# Sheet1.net
KiCad netlist of a schematic drawn in Altium Designer
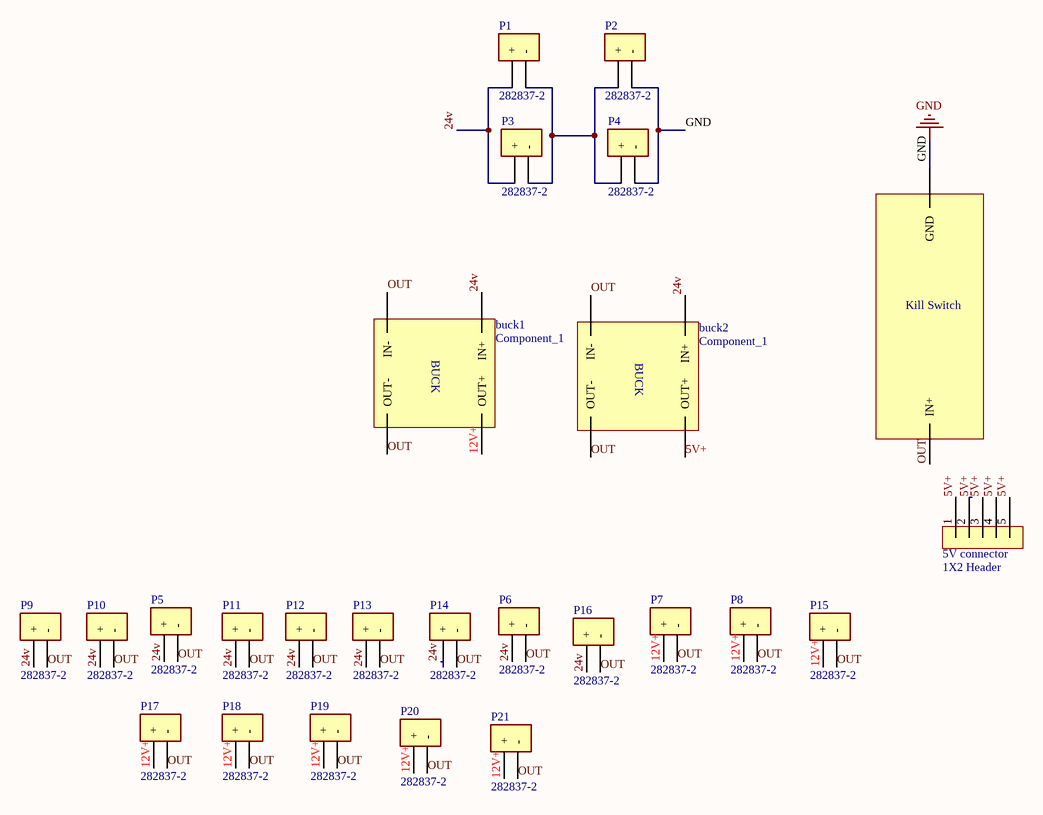
[diagram p0: Sheet1.SchDoc]

(export (version "E")
  (design (tool "Eeschema 10.0.6"))
  (components
    (comp (ref "5V connector")
      (value "1X2 Header")
      (footprint "Connector")
      (fields
        (field (name "MANUFACTURER") "TE Connectivity")
        (field (name "MANUFACTURER PART NUMBER") "640456-4")
      )
      (libsource (lib "282837-2") (part "640456-4"))
    )
    (comp (ref "buck1")
      (value "Component_1")
      (footprint "buck - duplicate")
      (libsource (lib "282837-2") (part "Component_1"))
    )
    (comp (ref "buck2")
      (value "Component_1")
      (footprint "buck - duplicate")
      (libsource (lib "282837-2") (part "Component_1"))
    )
    (comp (ref "KS") (value "KS") (footprint "KS") (libsource (lib "282837-2") (part "KS")))
    (comp (ref "P1")
      (value "282837-2")
      (footprint "TE_282837-2")
      (fields (field (name "MF") "TE Connectivity"))
      (libsource (lib "282837-2") (part "282837-2"))
    )
    (comp (ref "P2")
      (value "282837-2")
      (footprint "TE_282837-2")
      (fields (field (name "MF") "TE Connectivity"))
      (libsource (lib "282837-2") (part "282837-2"))
    )
    (comp (ref "P3")
      (value "282837-2")
      (footprint "TE_282837-2")
      (fields (field (name "MF") "TE Connectivity"))
      (libsource (lib "282837-2") (part "282837-2"))
    )
    (comp (ref "P4")
      (value "282837-2")
      (footprint "TE_282837-2")
      (fields (field (name "MF") "TE Connectivity"))
      (libsource (lib "282837-2") (part "282837-2"))
    )
    (comp (ref "P5")
      (value "282837-2")
      (footprint "TE_282837-2")
      (fields (field (name "MF") "TE Connectivity"))
      (libsource (lib "282837-2") (part "282837-2"))
    )
    (comp (ref "P6")
      (value "282837-2")
      (footprint "TE_282837-2")
      (fields (field (name "MF") "TE Connectivity"))
      (libsource (lib "282837-2") (part "282837-2"))
    )
    (comp (ref "P7")
      (value "282837-2")
      (footprint "TE_282837-2")
      (fields (field (name "MF") "TE Connectivity"))
      (libsource (lib "282837-2") (part "282837-2"))
    )
    (comp (ref "P8")
      (value "282837-2")
      (footprint "TE_282837-2")
      (fields (field (name "MF") "TE Connectivity"))
      (libsource (lib "282837-2") (part "282837-2"))
    )
    (comp (ref "P9")
      (value "282837-2")
      (footprint "TE_282837-2")
      (fields (field (name "MF") "TE Connectivity"))
      (libsource (lib "282837-2") (part "282837-2"))
    )
    (comp (ref "P10")
      (value "282837-2")
      (footprint "TE_282837-2")
      (fields (field (name "MF") "TE Connectivity"))
      (libsource (lib "282837-2") (part "282837-2"))
    )
    (comp (ref "P11")
      (value "282837-2")
      (footprint "TE_282837-2")
      (fields (field (name "MF") "TE Connectivity"))
      (libsource (lib "282837-2") (part "282837-2"))
    )
    (comp (ref "P12")
      (value "282837-2")
      (footprint "TE_282837-2")
      (fields (field (name "MF") "TE Connectivity"))
      (libsource (lib "282837-2") (part "282837-2"))
    )
    (comp (ref "P13")
      (value "282837-2")
      (footprint "TE_282837-2")
      (fields (field (name "MF") "TE Connectivity"))
      (libsource (lib "282837-2") (part "282837-2"))
    )
    (comp (ref "P14")
      (value "282837-2")
      (footprint "TE_282837-2")
      (fields (field (name "MF") "TE Connectivity"))
      (libsource (lib "282837-2") (part "282837-2"))
    )
    (comp (ref "P15")
      (value "282837-2")
      (footprint "TE_282837-2")
      (fields (field (name "MF") "TE Connectivity"))
      (libsource (lib "282837-2") (part "282837-2"))
    )
    (comp (ref "P16")
      (value "282837-2")
      (footprint "TE_282837-2")
      (fields (field (name "MF") "TE Connectivity"))
      (libsource (lib "282837-2") (part "282837-2"))
    )
    (comp (ref "P17")
      (value "282837-2")
      (footprint "TE_282837-2")
      (fields (field (name "MF") "TE Connectivity"))
      (libsource (lib "282837-2") (part "282837-2"))
    )
    (comp (ref "P18")
      (value "282837-2")
      (footprint "TE_282837-2")
      (fields (field (name "MF") "TE Connectivity"))
      (libsource (lib "282837-2") (part "282837-2"))
    )
    (comp (ref "P19")
      (value "282837-2")
      (footprint "TE_282837-2")
      (fields (field (name "MF") "TE Connectivity"))
      (libsource (lib "282837-2") (part "282837-2"))
    )
    (comp (ref "P20")
      (value "282837-2")
      (footprint "TE_282837-2")
      (fields (field (name "MF") "TE Connectivity"))
      (libsource (lib "282837-2") (part "282837-2"))
    )
    (comp (ref "P21")
      (value "282837-2")
      (footprint "TE_282837-2")
      (fields (field (name "MF") "TE Connectivity"))
      (libsource (lib "282837-2") (part "282837-2"))
    )
  )
  (nets
    (net (code "1") (name "/5V+") (class "Default")
      (node (ref "5V connector") (pin "1") (pinfunction "31_1") (pintype "passive"))
      (node (ref "5V connector") (pin "2") (pinfunction "32_2") (pintype "passive"))
      (node (ref "5V connector") (pin "3") (pinfunction "33_3") (pintype "passive"))
      (node (ref "5V connector") (pin "4") (pinfunction "34_4") (pintype "passive"))
      (node (ref "5V connector") (pin "5") (pinfunction "35_5") (pintype "passive"))
      (node (ref "buck2") (pin "4") (pinfunction "OUT+_4") (pintype "passive"))
    )
    (net (code "2") (name "/12V+") (class "Default")
      (node (ref "P15") (pin "1") (pinfunction "+_1") (pintype "passive"))
      (node (ref "P17") (pin "1") (pinfunction "+_1") (pintype "passive"))
      (node (ref "P18") (pin "1") (pinfunction "+_1") (pintype "passive"))
      (node (ref "P19") (pin "1") (pinfunction "+_1") (pintype "passive"))
      (node (ref "P20") (pin "1") (pinfunction "+_1") (pintype "passive"))
      (node (ref "P21") (pin "1") (pinfunction "+_1") (pintype "passive"))
      (node (ref "P7") (pin "1") (pinfunction "+_1") (pintype "passive"))
      (node (ref "P8") (pin "1") (pinfunction "+_1") (pintype "passive"))
      (node (ref "buck1") (pin "4") (pinfunction "OUT+_4") (pintype "passive"))
    )
    (net (code "3") (name "/24v") (class "Default")
      (node (ref "P1") (pin "1") (pinfunction "+_1") (pintype "passive"))
      (node (ref "P10") (pin "1") (pinfunction "+_1") (pintype "passive"))
      (node (ref "P11") (pin "1") (pinfunction "+_1") (pintype "passive"))
      (node (ref "P12") (pin "1") (pinfunction "+_1") (pintype "passive"))
      (node (ref "P13") (pin "1") (pinfunction "+_1") (pintype "passive"))
      (node (ref "P14") (pin "1") (pinfunction "+_1") (pintype "passive"))
      (node (ref "P16") (pin "1") (pinfunction "+_1") (pintype "passive"))
      (node (ref "P3") (pin "1") (pinfunction "+_1") (pintype "passive"))
      (node (ref "P5") (pin "1") (pinfunction "+_1") (pintype "passive"))
      (node (ref "P6") (pin "1") (pinfunction "+_1") (pintype "passive"))
      (node (ref "P9") (pin "1") (pinfunction "+_1") (pintype "passive"))
      (node (ref "buck1") (pin "2") (pinfunction "IN+_2") (pintype "passive"))
      (node (ref "buck2") (pin "2") (pinfunction "IN+_2") (pintype "passive"))
    )
    (net (code "5") (name "/OUT") (class "Default")
      (node (ref "KS") (pin "1") (pinfunction "IN+_1") (pintype "passive"))
      (node (ref "P10") (pin "2") (pinfunction "-_2") (pintype "passive"))
      (node (ref "P11") (pin "2") (pinfunction "-_2") (pintype "passive"))
      (node (ref "P12") (pin "2") (pinfunction "-_2") (pintype "passive"))
      (node (ref "P13") (pin "2") (pinfunction "-_2") (pintype "passive"))
      (node (ref "P14") (pin "2") (pinfunction "-_2") (pintype "passive"))
      (node (ref "P15") (pin "2") (pinfunction "-_2") (pintype "passive"))
      (node (ref "P16") (pin "2") (pinfunction "-_2") (pintype "passive"))
      (node (ref "P17") (pin "2") (pinfunction "-_2") (pintype "passive"))
      (node (ref "P18") (pin "2") (pinfunction "-_2") (pintype "passive"))
      (node (ref "P19") (pin "2") (pinfunction "-_2") (pintype "passive"))
      (node (ref "P20") (pin "2") (pinfunction "-_2") (pintype "passive"))
      (node (ref "P21") (pin "2") (pinfunction "-_2") (pintype "passive"))
      (node (ref "P5") (pin "2") (pinfunction "-_2") (pintype "passive"))
      (node (ref "P6") (pin "2") (pinfunction "-_2") (pintype "passive"))
      (node (ref "P7") (pin "2") (pinfunction "-_2") (pintype "passive"))
      (node (ref "P8") (pin "2") (pinfunction "-_2") (pintype "passive"))
      (node (ref "P9") (pin "2") (pinfunction "-_2") (pintype "passive"))
      (node (ref "buck1") (pin "1") (pinfunction "IN-_1") (pintype "passive"))
      (node (ref "buck1") (pin "3") (pinfunction "OUT-_3") (pintype "passive"))
      (node (ref "buck2") (pin "1") (pinfunction "IN-_1") (pintype "passive"))
      (node (ref "buck2") (pin "3") (pinfunction "OUT-_3") (pintype "passive"))
    )
    (net (code "6") (name "GND") (class "Default")
      (node (ref "KS") (pin "2") (pinfunction "GND_2") (pintype "passive"))
      (node (ref "P2") (pin "2") (pinfunction "-_2") (pintype "passive"))
      (node (ref "P4") (pin "2") (pinfunction "-_2") (pintype "passive"))
    )
    (net (code "7") (name "Net-(P1--)") (class "Default")
      (node (ref "P1") (pin "2") (pinfunction "-_2") (pintype "passive"))
      (node (ref "P2") (pin "1") (pinfunction "+_1") (pintype "passive"))
      (node (ref "P3") (pin "2") (pinfunction "-_2") (pintype "passive"))
      (node (ref "P4") (pin "1") (pinfunction "+_1") (pintype "passive"))
    )
  )
)
